# Temp_Meas.net
KiCad netlist of a schematic drawn in Altium Designer
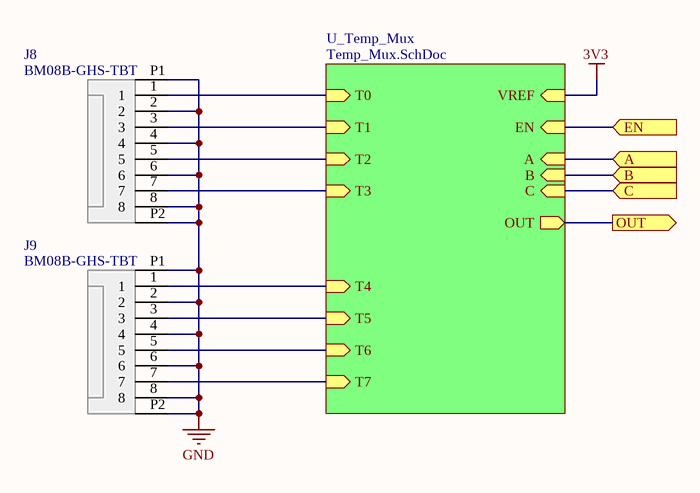
[diagram p0: Temp_Meas.SchDoc]

(export (version "E")
  (design (tool "Eeschema 10.0.6"))
  (components
    (comp (ref "J8")
      (value "BM08B-GHS-TBT")
      (footprint "J_BM08B-GHS-TBT")
      (description "Connector Header Surface Mount 8 position 0.049\" (1.25mm)")
      (fields
        (field (name "MANUFACTURER") "JST")
        (field (name "MANUFACTURER PART NUMBER") "BM08B-GHS-TBT(LF)(SN)")
      )
      (libsource (lib "connector") (part "J_BM08B-GHS-TBT"))
    )
    (comp (ref "J9")
      (value "BM08B-GHS-TBT")
      (footprint "J_BM08B-GHS-TBT")
      (description "Connector Header Surface Mount 8 position 0.049\" (1.25mm)")
      (fields
        (field (name "MANUFACTURER") "JST")
        (field (name "MANUFACTURER PART NUMBER") "BM08B-GHS-TBT(LF)(SN)")
      )
      (libsource (lib "connector") (part "J_BM08B-GHS-TBT"))
    )
  )
  (nets
    (net (code "6") (name "/T0") (class "Default")
      (node (ref "J8") (pin "1") (pinfunction "1_1") (pintype "passive"))
    )
    (net (code "7") (name "/T1") (class "Default")
      (node (ref "J8") (pin "3") (pinfunction "3_3") (pintype "passive"))
    )
    (net (code "8") (name "/T2") (class "Default")
      (node (ref "J8") (pin "5") (pinfunction "5_5") (pintype "passive"))
    )
    (net (code "9") (name "/T3") (class "Default")
      (node (ref "J8") (pin "7") (pinfunction "7_7") (pintype "passive"))
    )
    (net (code "10") (name "/T4") (class "Default")
      (node (ref "J9") (pin "1") (pinfunction "1_1") (pintype "passive"))
    )
    (net (code "11") (name "/T5") (class "Default")
      (node (ref "J9") (pin "3") (pinfunction "3_3") (pintype "passive"))
    )
    (net (code "12") (name "/T6") (class "Default")
      (node (ref "J9") (pin "5") (pinfunction "5_5") (pintype "passive"))
    )
    (net (code "13") (name "/T7") (class "Default")
      (node (ref "J9") (pin "7") (pinfunction "7_7") (pintype "passive"))
    )
    (net (code "15") (name "GND") (class "Default")
      (node (ref "J8") (pin "2") (pinfunction "2_2") (pintype "passive"))
      (node (ref "J8") (pin "4") (pinfunction "4_4") (pintype "passive"))
      (node (ref "J8") (pin "6") (pinfunction "6_6") (pintype "passive"))
      (node (ref "J8") (pin "8") (pinfunction "8_8") (pintype "passive"))
      (node (ref "J8") (pin "P1") (pinfunction "P1_P1") (pintype "passive"))
      (node (ref "J8") (pin "P2") (pinfunction "P2_P2") (pintype "passive"))
      (node (ref "J9") (pin "2") (pinfunction "2_2") (pintype "passive"))
      (node (ref "J9") (pin "4") (pinfunction "4_4") (pintype "passive"))
      (node (ref "J9") (pin "6") (pinfunction "6_6") (pintype "passive"))
      (node (ref "J9") (pin "8") (pinfunction "8_8") (pintype "passive"))
      (node (ref "J9") (pin "P1") (pinfunction "P1_P1") (pintype "passive"))
      (node (ref "J9") (pin "P2") (pinfunction "P2_P2") (pintype "passive"))
    )
  )
)
